# Bridge.net
KiCad netlist of a schematic drawn in Altium Designer
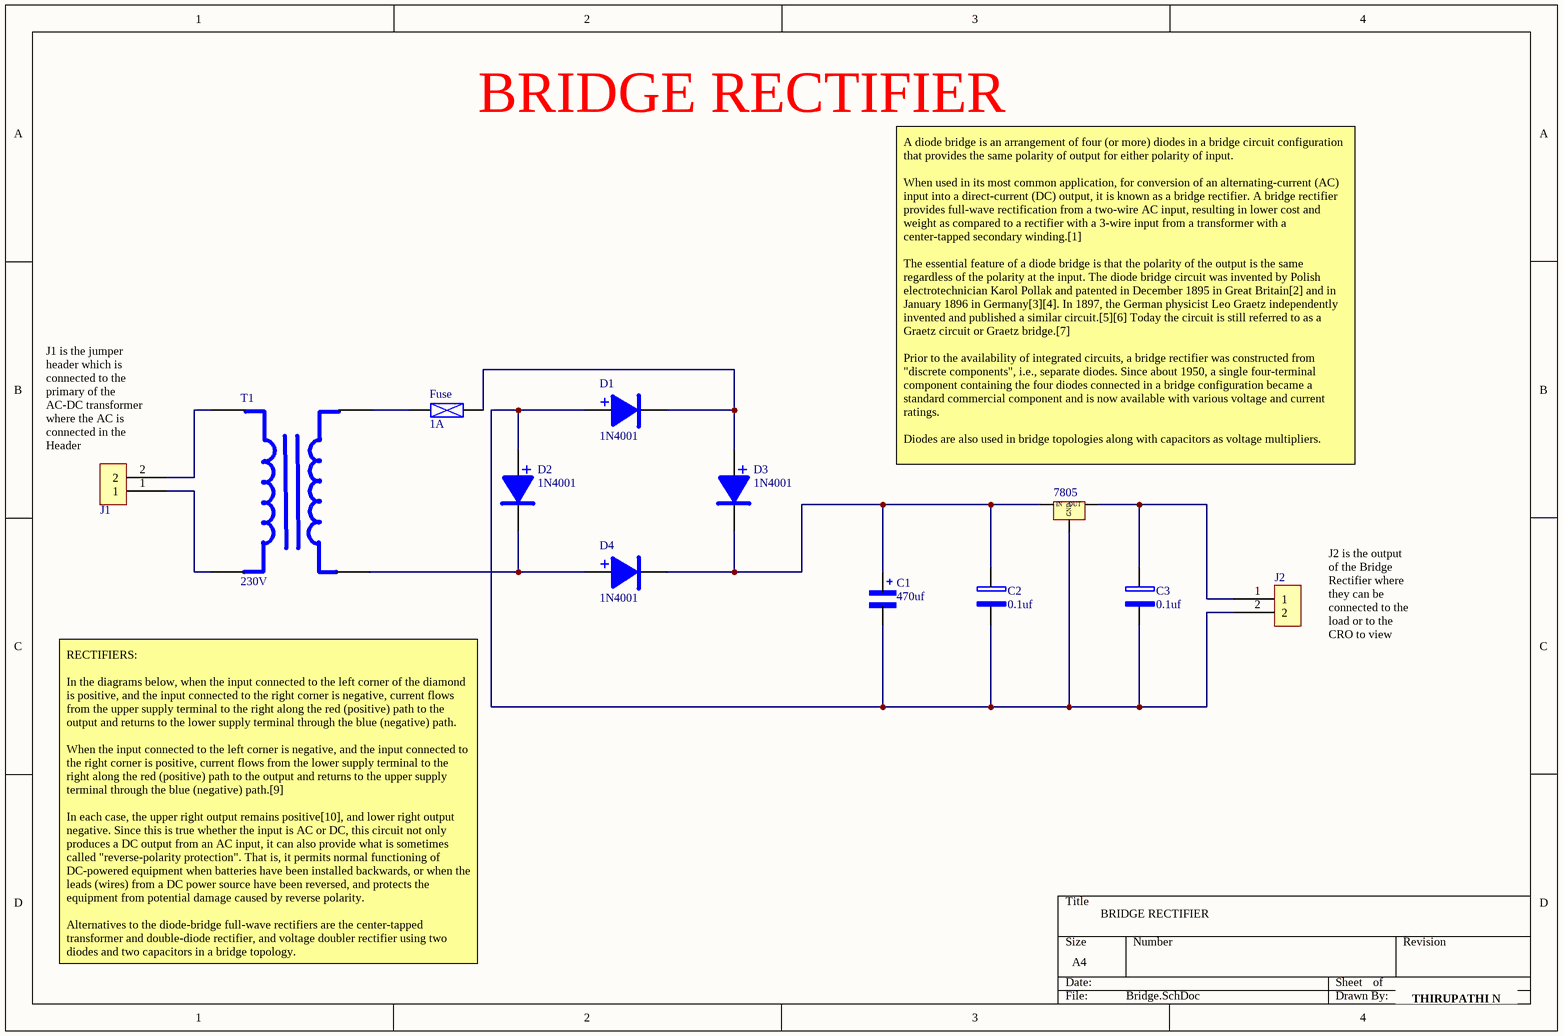
[diagram p0: Bridge.SchDoc]

(export (version "E")
  (design (tool "Eeschema 10.0.6"))
  (components
    (comp (ref "7805")
      (value "L78M05CDT-TR")
      (footprint "7805")
      (description "STMICROELECTRONICS - L78M05CDT-TR - VOLTAGE REG, FIXED, 5V, 0.5A, TO-252-3")
      (fields (field (name "MANUFACTURER") "STMicroelectronics") (field (name "TOLERANCE") "5%"))
      (libsource (lib "Bridge") (part "L78M05CDT-TR"))
    )
    (comp (ref "C1")
      (value "470uf")
      (footprint "470uf")
      (description "CAP CER 470UF 4V X5R 1812")
      (fields
        (field (name "MANUFACTURER") "Taiyo Yuden")
        (field (name "MANUFACTURER PART NUMBER") "AMK432BJ477MM-T")
      )
      (libsource (lib "Bridge") (part "470uf"))
    )
    (comp (ref "C2")
      (value "0.1uf")
      (footprint "0.1uf")
      (description "Multilayer Ceramic Capacitors MLCC - SMD/SMT 100nF 16V Y5V -20/+80%")
      (fields
        (field (name "MANUFACTURER") "Yageo")
        (field (name "MANUFACTURER PART NUMBER") "CC0402ZRY5V7BB104")
      )
      (libsource (lib "Bridge") (part "CC0402ZRY5V7BB104"))
    )
    (comp (ref "C3")
      (value "0.1uf")
      (footprint "0.1uf")
      (description "Multilayer Ceramic Capacitors MLCC - SMD/SMT 100nF 16V Y5V -20/+80%")
      (fields
        (field (name "MANUFACTURER") "Yageo")
        (field (name "MANUFACTURER PART NUMBER") "CC0402ZRY5V7BB104")
      )
      (libsource (lib "Bridge") (part "CC0402ZRY5V7BB104"))
    )
    (comp (ref "D1")
      (value "1N4001")
      (footprint "D1N4007")
      (description "DIODE GEN PURP 50V 1A DO41")
      (fields (field (name "MANUFACTURER") "ON Semiconductor / Fairchild"))
      (libsource (lib "Bridge") (part "1N4001"))
    )
    (comp (ref "D2")
      (value "1N4001")
      (footprint "D1N4007")
      (description "DIODE GEN PURP 50V 1A DO41")
      (fields (field (name "MANUFACTURER") "ON Semiconductor / Fairchild"))
      (libsource (lib "Bridge") (part "1N4001"))
    )
    (comp (ref "D3")
      (value "1N4001")
      (footprint "D1N4007")
      (description "DIODE GEN PURP 50V 1A DO41")
      (fields (field (name "MANUFACTURER") "ON Semiconductor / Fairchild"))
      (libsource (lib "Bridge") (part "1N4001"))
    )
    (comp (ref "D4")
      (value "1N4001")
      (footprint "D1N4007")
      (description "DIODE GEN PURP 50V 1A DO41")
      (fields (field (name "MANUFACTURER") "ON Semiconductor / Fairchild"))
      (libsource (lib "Bridge") (part "1N4001"))
    )
    (comp (ref "Fuse")
      (value "1A")
      (footprint "fuse")
      (description "FUSE BRD MNT 1A 125VAC/VDC")
      (fields (field (name "MANUFACTURER") "Bel") (field (name "MANUFACTURER PART NUMBER") "0679L1000-01"))
      (libsource (lib "Bridge") (part "0679L1000-01"))
    )
    (comp (ref "J1")
      (value "1986717-2")
      (footprint "Headder")
      (description "Headers & Wire Housings UNSHRDED STD HDR 3.5MM 2POS")
      (fields (field (name "MANUFACTURER") "TE Connectivity") (field (name "VOLTAGE") "150V"))
      (libsource (lib "Bridge") (part "1986717-2"))
    )
    (comp (ref "J2")
      (value "1986717-2")
      (footprint "Headder")
      (description "Headers & Wire Housings UNSHRDED STD HDR 3.5MM 2POS")
      (fields (field (name "MANUFACTURER") "TE Connectivity") (field (name "VOLTAGE") "150V"))
      (libsource (lib "") (part "1986717-2_1"))
    )
    (comp (ref "T1")
      (value "230V")
      (footprint "230V AC")
      (description "AC-DC; Converter; 4.2kV reg; Single Output; 5W; 12V Out; RAC05-K/277 Series")
      (fields
        (field (name "MANUFACTURER") "Recom")
        (field (name "MANUFACTURER PART NUMBER") "RAC05-12SK/277")
      )
      (libsource (lib "Bridge") (part "RAC05-12SK/277"))
    )
  )
  (nets
    (net (code "1") (name "Net-(7805-GND)") (class "Default")
      (node (ref "7805") (pin "2") (pinfunction "GND_2") (pintype "passive"))
      (node (ref "C1") (pin "2") (pinfunction "2_2") (pintype "passive"))
      (node (ref "C2") (pin "1") (pinfunction "1_1") (pintype "passive"))
      (node (ref "C3") (pin "1") (pinfunction "1_1") (pintype "passive"))
      (node (ref "D1") (pin "1") (pinfunction "1_1") (pintype "passive"))
      (node (ref "D2") (pin "1") (pinfunction "1_1") (pintype "passive"))
      (node (ref "J2") (pin "2") (pinfunction "2_2") (pintype "passive"))
    )
    (net (code "2") (name "Net-(7805-IN)") (class "Default")
      (node (ref "7805") (pin "1") (pinfunction "IN_1") (pintype "passive"))
      (node (ref "C1") (pin "1") (pinfunction "1_1") (pintype "passive"))
      (node (ref "C2") (pin "2") (pinfunction "2_2") (pintype "passive"))
      (node (ref "D3") (pin "2") (pinfunction "2_2") (pintype "passive"))
      (node (ref "D4") (pin "2") (pinfunction "2_2") (pintype "passive"))
    )
    (net (code "3") (name "Net-(7805-OUT)") (class "Default")
      (node (ref "7805") (pin "3") (pinfunction "OUT_3") (pintype "passive"))
      (node (ref "C3") (pin "2") (pinfunction "2_2") (pintype "passive"))
      (node (ref "J2") (pin "1") (pinfunction "1_1") (pintype "passive"))
    )
    (net (code "4") (name "Net-(D1-Pad2)") (class "Default")
      (node (ref "D1") (pin "2") (pinfunction "2_2") (pintype "passive"))
      (node (ref "D3") (pin "1") (pinfunction "1_1") (pintype "passive"))
      (node (ref "Fuse") (pin "1") (pinfunction "1_1") (pintype "passive"))
    )
    (net (code "5") (name "Net-(D2-Pad2)") (class "Default")
      (node (ref "D2") (pin "2") (pinfunction "2_2") (pintype "passive"))
      (node (ref "D4") (pin "1") (pinfunction "1_1") (pintype "passive"))
      (node (ref "T1") (pin "4") (pinfunction "4_4") (pintype "passive"))
    )
    (net (code "6") (name "Net-(Fuse-Pad2)") (class "Default")
      (node (ref "Fuse") (pin "2") (pinfunction "2_2") (pintype "passive"))
      (node (ref "T1") (pin "3") (pinfunction "3_3") (pintype "passive"))
    )
    (net (code "7") (name "Net-(J1-Pad1)") (class "Default")
      (node (ref "J1") (pin "1") (pinfunction "1_1") (pintype "passive"))
      (node (ref "T1") (pin "2") (pinfunction "2_2") (pintype "passive"))
    )
    (net (code "8") (name "Net-(J1-Pad2)") (class "Default")
      (node (ref "J1") (pin "2") (pinfunction "2_2") (pintype "passive"))
      (node (ref "T1") (pin "1") (pinfunction "1_1") (pintype "passive"))
    )
  )
)
